# linefollower.net
KiCad netlist of a schematic drawn in EAGLE
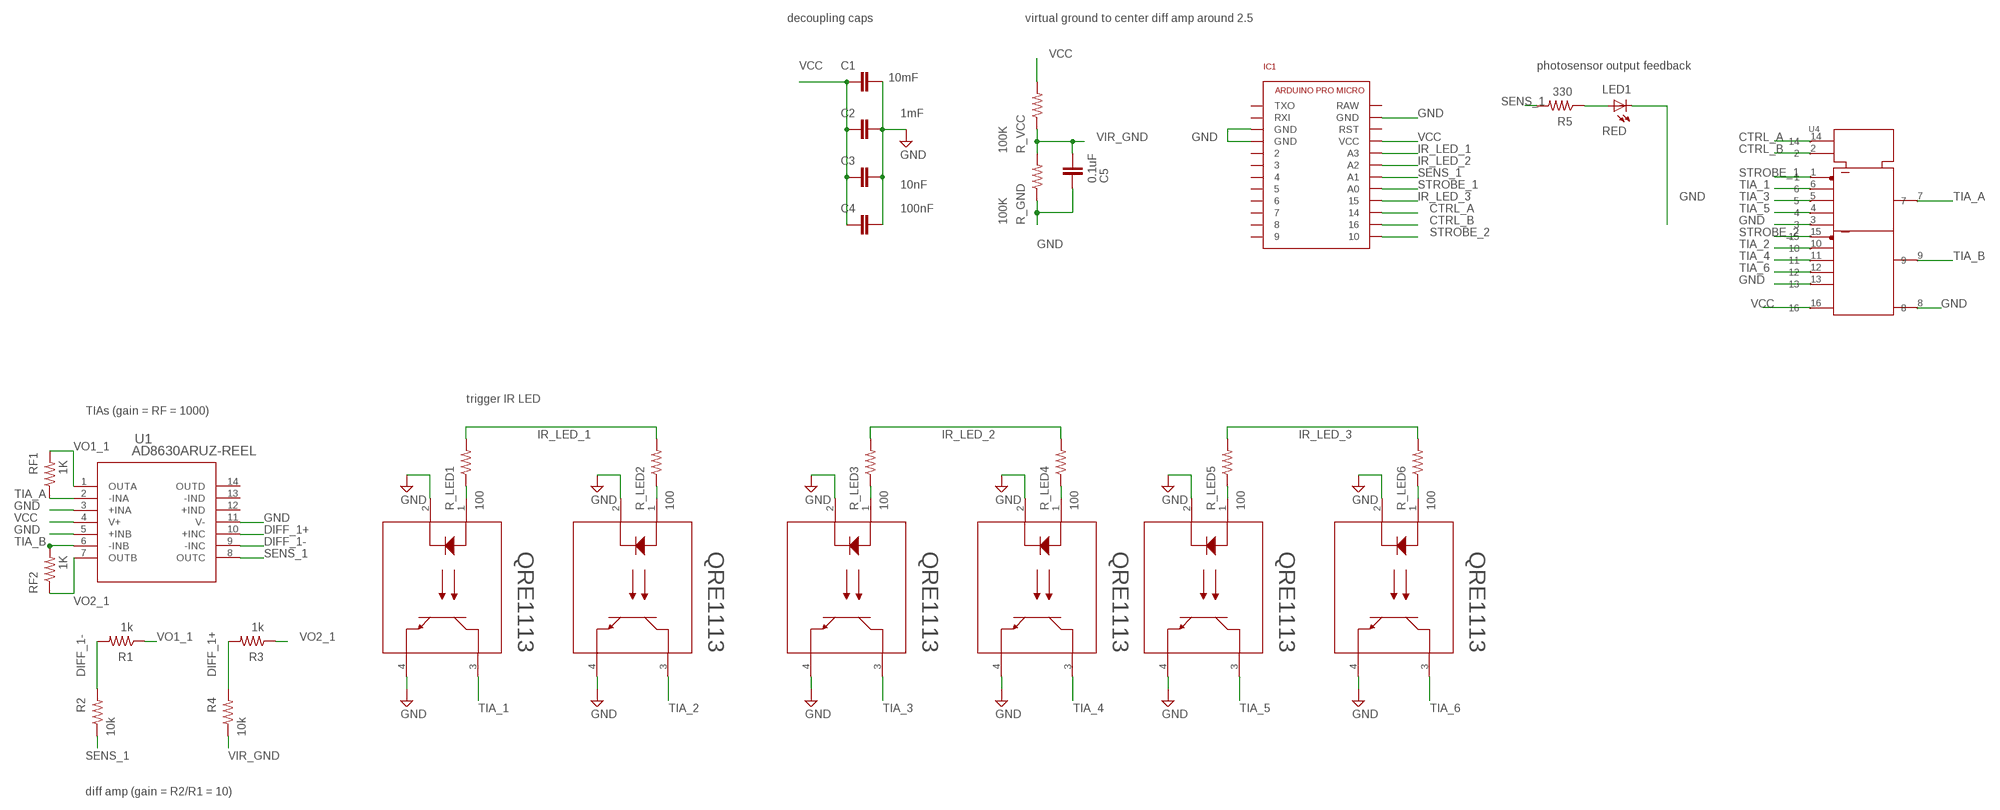
[diagram p0: schematic, sheet 1]

(export (version "E")
  (design (tool "Eeschema 10.0.6"))
  (components
    (comp (ref "C1")
      (value "10mF")
      (footprint "eagle-import:0402-CAP")
      (libsource (lib "eagle-import") (part "CAP0402-CAP"))
    )
    (comp (ref "C2")
      (value "1mF")
      (footprint "eagle-import:0402-CAP")
      (libsource (lib "eagle-import") (part "CAP0402-CAP"))
    )
    (comp (ref "C3")
      (value "10nF")
      (footprint "eagle-import:0402-CAP")
      (libsource (lib "eagle-import") (part "CAP0402-CAP"))
    )
    (comp (ref "C4")
      (value "100nF")
      (footprint "eagle-import:0402-CAP")
      (libsource (lib "eagle-import") (part "CAP0402-CAP"))
    )
    (comp (ref "C5")
      (value "0.1uF")
      (footprint "eagle-import:0402-CAP")
      (libsource (lib "eagle-import") (part "CAP0402-CAP"))
    )
    (comp (ref "IC1")
      (value "ARDUINO_PRO_MICRO")
      (footprint "eagle-import:ARDUINO_PRO_MICRO")
      (fields
        (field (name "DISTRIBUTOR_PART_NUMBER") "32284746884")
        (field (name "MANUFACTURER") "Feiyang electronics")
      )
      (libsource (lib "eagle-import") (part "ARDUINO_PRO_MICRO"))
    )
    (comp (ref "LED1")
      (value "RED")
      (footprint "eagle-import:LED-0603")
      (fields
        (field (name "DISTRIBUTOR_PART_NUMBER") "160-1415-1-ND")
        (field (name "MANUFACTURER") "Lite-On Inc")
        (field (name "MANUFACTURER_PART_NUMBER") "LTST-C170KRKT")
      )
      (libsource (lib "eagle-import") (part "LED0603"))
    )
    (comp (ref "Q1")
      (value "QRE1113")
      (footprint "eagle-import:DIP4_100AQ_ONS")
      (fields (field (name "COPYRIGHT") "Copyright (C) 2018 Accelerated Designs. All rights reserved"))
      (libsource (lib "eagle-import") (part "QRE1113"))
    )
    (comp (ref "Q2")
      (value "QRE1113")
      (footprint "eagle-import:DIP4_100AQ_ONS")
      (fields (field (name "COPYRIGHT") "Copyright (C) 2018 Accelerated Designs. All rights reserved"))
      (libsource (lib "eagle-import") (part "QRE1113"))
    )
    (comp (ref "Q3")
      (value "QRE1113")
      (footprint "eagle-import:DIP4_100AQ_ONS")
      (fields (field (name "COPYRIGHT") "Copyright (C) 2018 Accelerated Designs. All rights reserved"))
      (libsource (lib "eagle-import") (part "QRE1113"))
    )
    (comp (ref "Q4")
      (value "QRE1113")
      (footprint "eagle-import:DIP4_100AQ_ONS")
      (fields (field (name "COPYRIGHT") "Copyright (C) 2018 Accelerated Designs. All rights reserved"))
      (libsource (lib "eagle-import") (part "QRE1113"))
    )
    (comp (ref "Q5")
      (value "QRE1113")
      (footprint "eagle-import:DIP4_100AQ_ONS")
      (fields (field (name "COPYRIGHT") "Copyright (C) 2018 Accelerated Designs. All rights reserved"))
      (libsource (lib "eagle-import") (part "QRE1113"))
    )
    (comp (ref "Q6")
      (value "QRE1113")
      (footprint "eagle-import:DIP4_100AQ_ONS")
      (fields (field (name "COPYRIGHT") "Copyright (C) 2018 Accelerated Designs. All rights reserved"))
      (libsource (lib "eagle-import") (part "QRE1113"))
    )
    (comp (ref "R1")
      (value "1k")
      (footprint "eagle-import:R0603")
      (fields (field (name "MANUFACTURER") "Rohm Semiconductor"))
      (libsource (lib "eagle-import") (part "R-US_R0603"))
    )
    (comp (ref "R2")
      (value "10k")
      (footprint "eagle-import:R0603")
      (fields (field (name "MANUFACTURER") "Rohm Semiconductor"))
      (libsource (lib "eagle-import") (part "R-US_R0603"))
    )
    (comp (ref "R3")
      (value "1k")
      (footprint "eagle-import:R0603")
      (fields (field (name "MANUFACTURER") "Rohm Semiconductor"))
      (libsource (lib "eagle-import") (part "R-US_R0603"))
    )
    (comp (ref "R4")
      (value "10k")
      (footprint "eagle-import:R0603")
      (fields (field (name "MANUFACTURER") "Rohm Semiconductor"))
      (libsource (lib "eagle-import") (part "R-US_R0603"))
    )
    (comp (ref "R5")
      (value "330")
      (footprint "eagle-import:R0603")
      (fields (field (name "MANUFACTURER") "Rohm Semiconductor"))
      (libsource (lib "eagle-import") (part "R-US_R0603"))
    )
    (comp (ref "RF1")
      (value "1K")
      (footprint "eagle-import:R0603")
      (fields (field (name "MANUFACTURER") "Rohm Semiconductor"))
      (libsource (lib "eagle-import") (part "R-US_R0603"))
    )
    (comp (ref "RF2")
      (value "1K")
      (footprint "eagle-import:R0603")
      (fields (field (name "MANUFACTURER") "Rohm Semiconductor"))
      (libsource (lib "eagle-import") (part "R-US_R0603"))
    )
    (comp (ref "R_GND")
      (value "100K")
      (footprint "eagle-import:R0603")
      (fields (field (name "MANUFACTURER") "Rohm Semiconductor"))
      (libsource (lib "eagle-import") (part "R-US_R0603"))
    )
    (comp (ref "R_LED1")
      (value "100")
      (footprint "eagle-import:R0603")
      (fields (field (name "MANUFACTURER") "Rohm Semiconductor"))
      (libsource (lib "eagle-import") (part "R-US_R0603"))
    )
    (comp (ref "R_LED2")
      (value "100")
      (footprint "eagle-import:R0603")
      (fields (field (name "MANUFACTURER") "Rohm Semiconductor"))
      (libsource (lib "eagle-import") (part "R-US_R0603"))
    )
    (comp (ref "R_LED3")
      (value "100")
      (footprint "eagle-import:R0603")
      (fields (field (name "MANUFACTURER") "Rohm Semiconductor"))
      (libsource (lib "eagle-import") (part "R-US_R0603"))
    )
    (comp (ref "R_LED4")
      (value "100")
      (footprint "eagle-import:R0603")
      (fields (field (name "MANUFACTURER") "Rohm Semiconductor"))
      (libsource (lib "eagle-import") (part "R-US_R0603"))
    )
    (comp (ref "R_LED5")
      (value "100")
      (footprint "eagle-import:R0603")
      (fields (field (name "MANUFACTURER") "Rohm Semiconductor"))
      (libsource (lib "eagle-import") (part "R-US_R0603"))
    )
    (comp (ref "R_LED6")
      (value "100")
      (footprint "eagle-import:R0603")
      (fields (field (name "MANUFACTURER") "Rohm Semiconductor"))
      (libsource (lib "eagle-import") (part "R-US_R0603"))
    )
    (comp (ref "R_VCC")
      (value "100K")
      (footprint "eagle-import:R0603")
      (fields (field (name "MANUFACTURER") "Rohm Semiconductor"))
      (libsource (lib "eagle-import") (part "R-US_R0603"))
    )
    (comp (ref "U1")
      (value "AD8630ARUZ-REEL")
      (footprint "eagle-import:RU_14_ADI")
      (fields (field (name "COPYRIGHT") "Copyright (C) 2016 Accelerated Designs. All rights reserved"))
      (libsource (lib "eagle-import") (part "AD8630ARUZ-REEL"))
    )
    (comp (ref "U4")
      (value "74VHC153FT(BJ)")
      (footprint "eagle-import:TSSOP16B_TOS")
      (fields (field (name "COPYRIGHT") "Copyright (C) 2018 Accelerated Designs. All rights reserved"))
      (libsource (lib "eagle-import") (part "74VHC153FT(BJ)"))
    )
  )
  (nets
    (net (code "1") (name "/CTRL_A") (class "Default")
      (node (ref "IC1") (pin "14") (pinfunction "14_14") (pintype "bidirectional"))
      (node (ref "U4") (pin "14") (pinfunction "14_14") (pintype "passive"))
    )
    (net (code "2") (name "/CTRL_B") (class "Default")
      (node (ref "IC1") (pin "16") (pinfunction "16_16") (pintype "bidirectional"))
      (node (ref "U4") (pin "2") (pinfunction "2_2") (pintype "passive"))
    )
    (net (code "3") (name "/DIFF_1+") (class "Default")
      (node (ref "R3") (pin "2") (pinfunction "2_2") (pintype "passive"))
      (node (ref "R4") (pin "2") (pinfunction "2_2") (pintype "passive"))
      (node (ref "U1") (pin "10") (pinfunction "+INC_10") (pintype "input"))
    )
    (net (code "4") (name "/DIFF_1-") (class "Default")
      (node (ref "R1") (pin "2") (pinfunction "2_2") (pintype "passive"))
      (node (ref "R2") (pin "2") (pinfunction "2_2") (pintype "passive"))
      (node (ref "U1") (pin "9") (pinfunction "-INC_9") (pintype "input"))
    )
    (net (code "5") (name "/IR_LED_1") (class "Default")
      (node (ref "IC1") (pin "A3") (pinfunction "A3_A3") (pintype "bidirectional"))
      (node (ref "R_LED1") (pin "2") (pinfunction "2_2") (pintype "passive"))
      (node (ref "R_LED2") (pin "2") (pinfunction "2_2") (pintype "passive"))
    )
    (net (code "6") (name "/IR_LED_2") (class "Default")
      (node (ref "IC1") (pin "A2") (pinfunction "A2_A2") (pintype "bidirectional"))
      (node (ref "R_LED3") (pin "2") (pinfunction "2_2") (pintype "passive"))
      (node (ref "R_LED4") (pin "2") (pinfunction "2_2") (pintype "passive"))
    )
    (net (code "7") (name "/IR_LED_3") (class "Default")
      (node (ref "IC1") (pin "15") (pinfunction "15_15") (pintype "bidirectional"))
      (node (ref "R_LED5") (pin "2") (pinfunction "2_2") (pintype "passive"))
      (node (ref "R_LED6") (pin "2") (pinfunction "2_2") (pintype "passive"))
    )
    (net (code "8") (name "/SENS_1") (class "Default")
      (node (ref "IC1") (pin "A1") (pinfunction "A1_A1") (pintype "bidirectional"))
      (node (ref "R2") (pin "1") (pinfunction "1_1") (pintype "passive"))
      (node (ref "R5") (pin "2") (pinfunction "2_2") (pintype "passive"))
      (node (ref "U1") (pin "8") (pinfunction "OUTC_8") (pintype "output"))
    )
    (net (code "9") (name "/STROBE_1") (class "Default")
      (node (ref "IC1") (pin "A0") (pinfunction "A0_A0") (pintype "bidirectional"))
      (node (ref "U4") (pin "1") (pinfunction "1_1") (pintype "passive"))
    )
    (net (code "10") (name "/STROBE_2") (class "Default")
      (node (ref "IC1") (pin "10") (pinfunction "10_10") (pintype "bidirectional"))
      (node (ref "U4") (pin "15") (pinfunction "15_15") (pintype "passive"))
    )
    (net (code "11") (name "/TIA_1") (class "Default")
      (node (ref "Q1") (pin "3") (pinfunction "3_3") (pintype "passive"))
      (node (ref "U4") (pin "6") (pinfunction "6_6") (pintype "passive"))
    )
    (net (code "12") (name "/TIA_2") (class "Default")
      (node (ref "Q2") (pin "3") (pinfunction "3_3") (pintype "passive"))
      (node (ref "U4") (pin "10") (pinfunction "10_10") (pintype "passive"))
    )
    (net (code "13") (name "/TIA_3") (class "Default")
      (node (ref "Q3") (pin "3") (pinfunction "3_3") (pintype "passive"))
      (node (ref "U4") (pin "5") (pinfunction "5_5") (pintype "passive"))
    )
    (net (code "14") (name "/TIA_4") (class "Default")
      (node (ref "Q4") (pin "3") (pinfunction "3_3") (pintype "passive"))
      (node (ref "U4") (pin "11") (pinfunction "11_11") (pintype "passive"))
    )
    (net (code "15") (name "/TIA_5") (class "Default")
      (node (ref "Q5") (pin "3") (pinfunction "3_3") (pintype "passive"))
      (node (ref "U4") (pin "4") (pinfunction "4_4") (pintype "passive"))
    )
    (net (code "16") (name "/TIA_6") (class "Default")
      (node (ref "Q6") (pin "3") (pinfunction "3_3") (pintype "passive"))
      (node (ref "U4") (pin "12") (pinfunction "12_12") (pintype "passive"))
    )
    (net (code "17") (name "/TIA_A") (class "Default")
      (node (ref "RF1") (pin "1") (pinfunction "1_1") (pintype "passive"))
      (node (ref "U1") (pin "2") (pinfunction "-INA_2") (pintype "input"))
      (node (ref "U4") (pin "7") (pinfunction "7_7") (pintype "passive"))
    )
    (net (code "18") (name "/TIA_B") (class "Default")
      (node (ref "RF2") (pin "2") (pinfunction "2_2") (pintype "passive"))
      (node (ref "U1") (pin "6") (pinfunction "-INB_6") (pintype "input"))
      (node (ref "U4") (pin "9") (pinfunction "9_9") (pintype "passive"))
    )
    (net (code "19") (name "/VCC") (class "Default")
      (node (ref "C1") (pin "1") (pinfunction "1_1") (pintype "passive"))
      (node (ref "C2") (pin "1") (pinfunction "1_1") (pintype "passive"))
      (node (ref "C3") (pin "1") (pinfunction "1_1") (pintype "passive"))
      (node (ref "C4") (pin "1") (pinfunction "1_1") (pintype "passive"))
      (node (ref "IC1") (pin "VCC") (pinfunction "VCC_VCC") (pintype "bidirectional"))
      (node (ref "R_VCC") (pin "2") (pinfunction "2_2") (pintype "passive"))
      (node (ref "U1") (pin "4") (pinfunction "V+_4") (pintype "power_in"))
      (node (ref "U4") (pin "16") (pinfunction "16_16") (pintype "passive"))
    )
    (net (code "20") (name "/VIR_GND") (class "Default")
      (node (ref "C5") (pin "2") (pinfunction "2_2") (pintype "passive"))
      (node (ref "R4") (pin "1") (pinfunction "1_1") (pintype "passive"))
      (node (ref "R_GND") (pin "2") (pinfunction "2_2") (pintype "passive"))
      (node (ref "R_VCC") (pin "1") (pinfunction "1_1") (pintype "passive"))
    )
    (net (code "21") (name "/VO1_1") (class "Default")
      (node (ref "R1") (pin "1") (pinfunction "1_1") (pintype "passive"))
      (node (ref "RF1") (pin "2") (pinfunction "2_2") (pintype "passive"))
      (node (ref "U1") (pin "1") (pinfunction "OUTA_1") (pintype "output"))
    )
    (net (code "22") (name "/VO2_1") (class "Default")
      (node (ref "R3") (pin "1") (pinfunction "1_1") (pintype "passive"))
      (node (ref "RF2") (pin "1") (pinfunction "1_1") (pintype "passive"))
      (node (ref "U1") (pin "7") (pinfunction "OUTB_7") (pintype "output"))
    )
    (net (code "23") (name "GND") (class "Default")
      (node (ref "C1") (pin "2") (pinfunction "2_2") (pintype "passive"))
      (node (ref "C2") (pin "2") (pinfunction "2_2") (pintype "passive"))
      (node (ref "C3") (pin "2") (pinfunction "2_2") (pintype "passive"))
      (node (ref "C4") (pin "2") (pinfunction "2_2") (pintype "passive"))
      (node (ref "C5") (pin "1") (pinfunction "1_1") (pintype "passive"))
      (node (ref "IC1") (pin "GND@0") (pinfunction "GND_GND@0") (pintype "bidirectional"))
      (node (ref "IC1") (pin "GND@1") (pinfunction "GND_GND@1") (pintype "bidirectional"))
      (node (ref "IC1") (pin "GND@2") (pinfunction "GND_GND@2") (pintype "bidirectional"))
      (node (ref "LED1") (pin "C") (pinfunction "C_C") (pintype "passive"))
      (node (ref "Q1") (pin "2") (pinfunction "2_2") (pintype "passive"))
      (node (ref "Q1") (pin "4") (pinfunction "4_4") (pintype "passive"))
      (node (ref "Q2") (pin "2") (pinfunction "2_2") (pintype "passive"))
      (node (ref "Q2") (pin "4") (pinfunction "4_4") (pintype "passive"))
      (node (ref "Q3") (pin "2") (pinfunction "2_2") (pintype "passive"))
      (node (ref "Q3") (pin "4") (pinfunction "4_4") (pintype "passive"))
      (node (ref "Q4") (pin "2") (pinfunction "2_2") (pintype "passive"))
      (node (ref "Q4") (pin "4") (pinfunction "4_4") (pintype "passive"))
      (node (ref "Q5") (pin "2") (pinfunction "2_2") (pintype "passive"))
      (node (ref "Q5") (pin "4") (pinfunction "4_4") (pintype "passive"))
      (node (ref "Q6") (pin "2") (pinfunction "2_2") (pintype "passive"))
      (node (ref "Q6") (pin "4") (pinfunction "4_4") (pintype "passive"))
      (node (ref "R_GND") (pin "1") (pinfunction "1_1") (pintype "passive"))
      (node (ref "U1") (pin "11") (pinfunction "V-_11") (pintype "power_in"))
      (node (ref "U1") (pin "3") (pinfunction "+INA_3") (pintype "input"))
      (node (ref "U1") (pin "5") (pinfunction "+INB_5") (pintype "input"))
      (node (ref "U4") (pin "13") (pinfunction "13_13") (pintype "passive"))
      (node (ref "U4") (pin "3") (pinfunction "3_3") (pintype "passive"))
      (node (ref "U4") (pin "8") (pinfunction "8_8") (pintype "passive"))
    )
    (net (code "24") (name "Net-(LED1-PadA)") (class "Default")
      (node (ref "LED1") (pin "A") (pinfunction "A_A") (pintype "passive"))
      (node (ref "R5") (pin "1") (pinfunction "1_1") (pintype "passive"))
    )
    (net (code "25") (name "Net-(Q1-Pad1)") (class "Default")
      (node (ref "Q1") (pin "1") (pinfunction "1_1") (pintype "passive"))
      (node (ref "R_LED1") (pin "1") (pinfunction "1_1") (pintype "passive"))
    )
    (net (code "26") (name "Net-(Q2-Pad1)") (class "Default")
      (node (ref "Q2") (pin "1") (pinfunction "1_1") (pintype "passive"))
      (node (ref "R_LED2") (pin "1") (pinfunction "1_1") (pintype "passive"))
    )
    (net (code "27") (name "Net-(Q3-Pad1)") (class "Default")
      (node (ref "Q3") (pin "1") (pinfunction "1_1") (pintype "passive"))
      (node (ref "R_LED3") (pin "1") (pinfunction "1_1") (pintype "passive"))
    )
    (net (code "28") (name "Net-(Q4-Pad1)") (class "Default")
      (node (ref "Q4") (pin "1") (pinfunction "1_1") (pintype "passive"))
      (node (ref "R_LED4") (pin "1") (pinfunction "1_1") (pintype "passive"))
    )
    (net (code "29") (name "Net-(Q5-Pad1)") (class "Default")
      (node (ref "Q5") (pin "1") (pinfunction "1_1") (pintype "passive"))
      (node (ref "R_LED5") (pin "1") (pinfunction "1_1") (pintype "passive"))
    )
    (net (code "30") (name "Net-(Q6-Pad1)") (class "Default")
      (node (ref "Q6") (pin "1") (pinfunction "1_1") (pintype "passive"))
      (node (ref "R_LED6") (pin "1") (pinfunction "1_1") (pintype "passive"))
    )
    (net (code "31") (name "unconnected-(IC1-Pad2)") (class "Default")
      (node (ref "IC1") (pin "2") (pinfunction "2_2") (pintype "bidirectional"))
    )
    (net (code "32") (name "unconnected-(IC1-Pad3)") (class "Default")
      (node (ref "IC1") (pin "3") (pinfunction "3_3") (pintype "bidirectional"))
    )
    (net (code "33") (name "unconnected-(IC1-Pad4)") (class "Default")
      (node (ref "IC1") (pin "4") (pinfunction "4_4") (pintype "bidirectional"))
    )
    (net (code "34") (name "unconnected-(IC1-Pad5)") (class "Default")
      (node (ref "IC1") (pin "5") (pinfunction "5_5") (pintype "bidirectional"))
    )
    (net (code "35") (name "unconnected-(IC1-Pad6)") (class "Default")
      (node (ref "IC1") (pin "6") (pinfunction "6_6") (pintype "bidirectional"))
    )
    (net (code "36") (name "unconnected-(IC1-Pad7)") (class "Default")
      (node (ref "IC1") (pin "7") (pinfunction "7_7") (pintype "bidirectional"))
    )
    (net (code "37") (name "unconnected-(IC1-Pad8)") (class "Default")
      (node (ref "IC1") (pin "8") (pinfunction "8_8") (pintype "bidirectional"))
    )
    (net (code "38") (name "unconnected-(IC1-Pad9)") (class "Default")
      (node (ref "IC1") (pin "9") (pinfunction "9_9") (pintype "bidirectional"))
    )
    (net (code "39") (name "unconnected-(IC1-PadRAW)") (class "Default")
      (node (ref "IC1") (pin "RAW") (pinfunction "RAW_RAW") (pintype "bidirectional"))
    )
    (net (code "40") (name "unconnected-(IC1-PadRST)") (class "Default")
      (node (ref "IC1") (pin "RST") (pinfunction "RST_RST") (pintype "bidirectional"))
    )
    (net (code "41") (name "unconnected-(IC1-PadRXI)") (class "Default")
      (node (ref "IC1") (pin "RXI") (pinfunction "RXI_RXI") (pintype "bidirectional"))
    )
    (net (code "42") (name "unconnected-(IC1-PadTXO)") (class "Default")
      (node (ref "IC1") (pin "TXO") (pinfunction "TXO_TXO") (pintype "bidirectional"))
    )
    (net (code "43") (name "unconnected-(U1-+IND-Pad12)") (class "Default")
      (node (ref "U1") (pin "12") (pinfunction "+IND_12") (pintype "input"))
    )
    (net (code "44") (name "unconnected-(U1--IND-Pad13)") (class "Default")
      (node (ref "U1") (pin "13") (pinfunction "-IND_13") (pintype "input"))
    )
    (net (code "45") (name "unconnected-(U1-OUTD-Pad14)") (class "Default")
      (node (ref "U1") (pin "14") (pinfunction "OUTD_14") (pintype "output"))
    )
  )
)
